# schematic.net
KiCad netlist of a schematic drawn in EAGLE
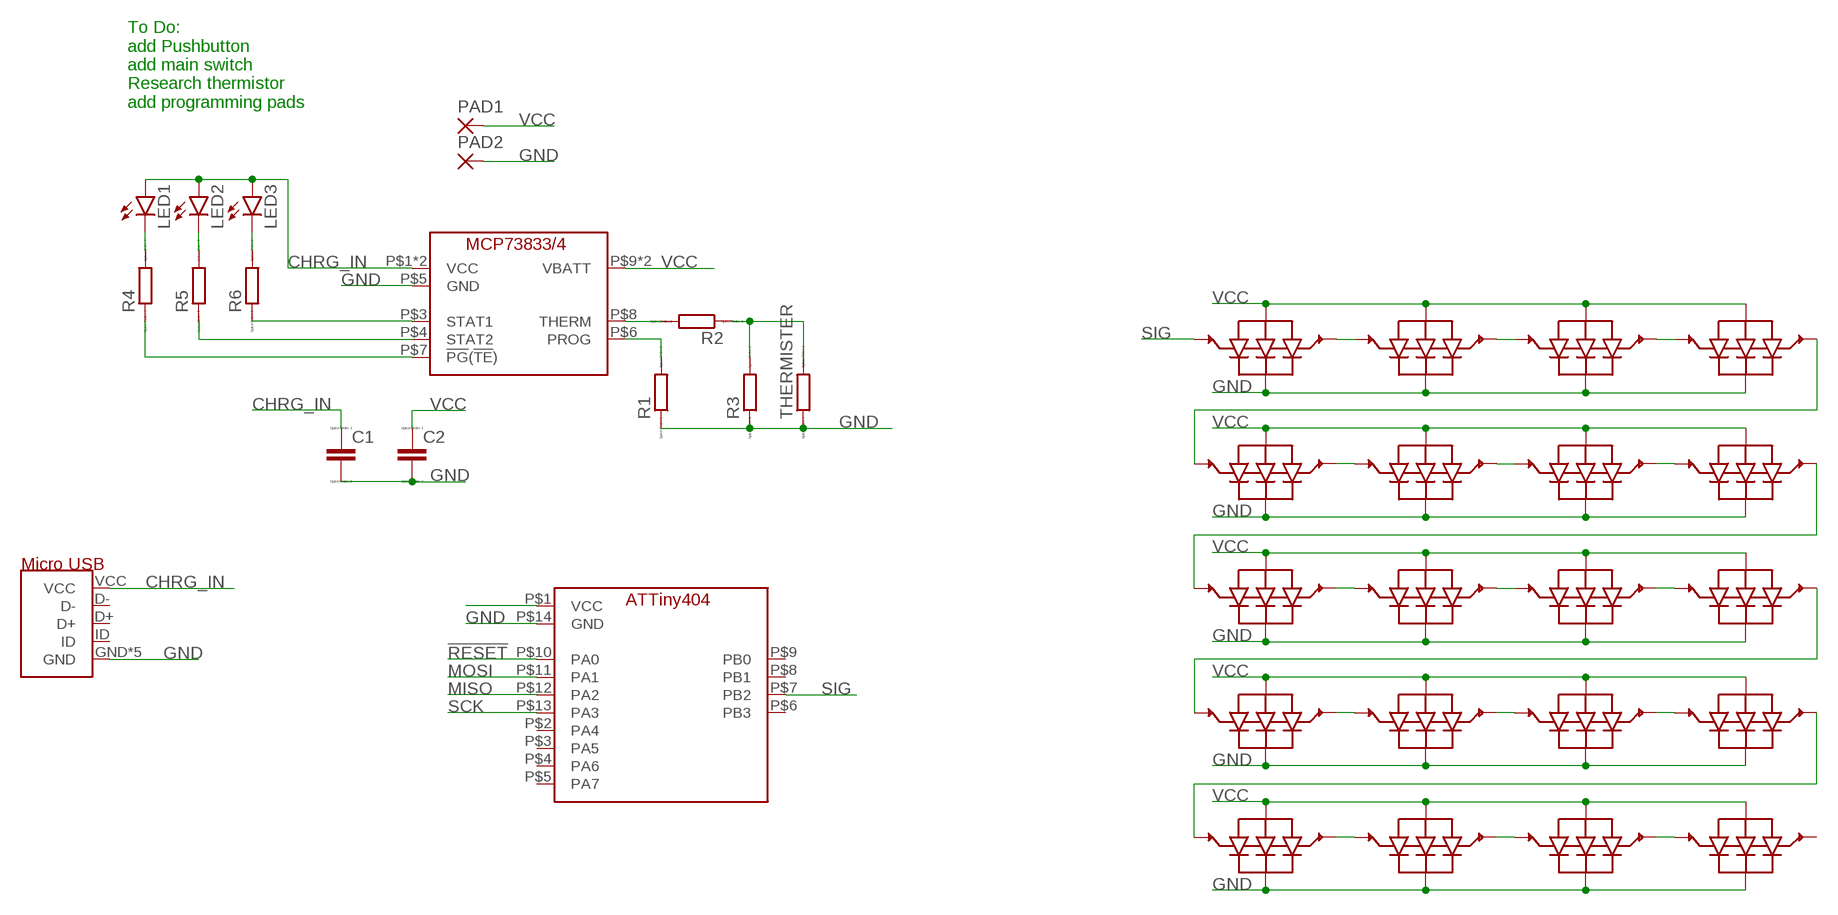
[diagram p0: schematic, sheet 1]

(export (version "E")
  (design (tool "Eeschema 10.0.6"))
  (components
    (comp (ref "C1")
      (value "CC1206")
      (footprint "eagle-import:C1206")
      (libsource (lib "eagle-import") (part "CC1206"))
    )
    (comp (ref "C2")
      (value "CC1206")
      (footprint "eagle-import:C1206")
      (libsource (lib "eagle-import") (part "CC1206"))
    )
    (comp (ref "LED1")
      (value "LEDSML1206")
      (footprint "eagle-import:SML1206")
      (libsource (lib "eagle-import") (part "LEDSML1206"))
    )
    (comp (ref "LED2")
      (value "LEDSML1206")
      (footprint "eagle-import:SML1206")
      (libsource (lib "eagle-import") (part "LEDSML1206"))
    )
    (comp (ref "LED3")
      (value "LEDSML1206")
      (footprint "eagle-import:SML1206")
      (libsource (lib "eagle-import") (part "LEDSML1206"))
    )
    (comp (ref "PAD1")
      (value "1,6/0,8")
      (footprint "eagle-import:1,6_0,8")
      (libsource (lib "eagle-import") (part "1,6/0,8"))
    )
    (comp (ref "PAD2")
      (value "1,6/0,8")
      (footprint "eagle-import:1,6_0,8")
      (libsource (lib "eagle-import") (part "1,6/0,8"))
    )
    (comp (ref "R1")
      (value "RR1206")
      (footprint "eagle-import:R1206")
      (libsource (lib "eagle-import") (part "RR1206"))
    )
    (comp (ref "R2")
      (value "RR1206")
      (footprint "eagle-import:R1206")
      (libsource (lib "eagle-import") (part "RR1206"))
    )
    (comp (ref "R3")
      (value "RR1206")
      (footprint "eagle-import:R1206")
      (libsource (lib "eagle-import") (part "RR1206"))
    )
    (comp (ref "R4")
      (value "RR1206")
      (footprint "eagle-import:R1206")
      (libsource (lib "eagle-import") (part "RR1206"))
    )
    (comp (ref "R5")
      (value "RR1206")
      (footprint "eagle-import:R1206")
      (libsource (lib "eagle-import") (part "RR1206"))
    )
    (comp (ref "R6")
      (value "RR1206")
      (footprint "eagle-import:R1206")
      (libsource (lib "eagle-import") (part "RR1206"))
    )
    (comp (ref "THERMISTER")
      (value "RR1206")
      (footprint "eagle-import:R1206")
      (libsource (lib "eagle-import") (part "RR1206"))
    )
    (comp (ref "U$1")
      (value "ATTINY404")
      (footprint "eagle-import:14-SOIC")
      (libsource (lib "eagle-import") (part "ATTINY404"))
    )
    (comp (ref "U$2")
      (value "MCP73833/4")
      (footprint "eagle-import:10-MSOP")
      (libsource (lib "eagle-import") (part "MCP73833/4"))
    )
    (comp (ref "U$3")
      (value "WS2812B")
      (footprint "eagle-import:5050-THRU")
      (libsource (lib "eagle-import") (part "WS2812B"))
    )
    (comp (ref "U$4")
      (value "WS2812B")
      (footprint "eagle-import:5050-THRU")
      (libsource (lib "eagle-import") (part "WS2812B"))
    )
    (comp (ref "U$5")
      (value "WS2812B")
      (footprint "eagle-import:5050-THRU")
      (libsource (lib "eagle-import") (part "WS2812B"))
    )
    (comp (ref "U$6")
      (value "WS2812B")
      (footprint "eagle-import:5050-THRU")
      (libsource (lib "eagle-import") (part "WS2812B"))
    )
    (comp (ref "U$7")
      (value "WS2812B")
      (footprint "eagle-import:5050-THRU")
      (libsource (lib "eagle-import") (part "WS2812B"))
    )
    (comp (ref "U$8")
      (value "WS2812B")
      (footprint "eagle-import:5050-THRU")
      (libsource (lib "eagle-import") (part "WS2812B"))
    )
    (comp (ref "U$9")
      (value "WS2812B")
      (footprint "eagle-import:5050-THRU")
      (libsource (lib "eagle-import") (part "WS2812B"))
    )
    (comp (ref "U$10")
      (value "WS2812B")
      (footprint "eagle-import:5050-THRU")
      (libsource (lib "eagle-import") (part "WS2812B"))
    )
    (comp (ref "U$11")
      (value "WS2812B")
      (footprint "eagle-import:5050-THRU")
      (libsource (lib "eagle-import") (part "WS2812B"))
    )
    (comp (ref "U$12")
      (value "WS2812B")
      (footprint "eagle-import:5050-THRU")
      (libsource (lib "eagle-import") (part "WS2812B"))
    )
    (comp (ref "U$13")
      (value "WS2812B")
      (footprint "eagle-import:5050-THRU")
      (libsource (lib "eagle-import") (part "WS2812B"))
    )
    (comp (ref "U$14")
      (value "WS2812B")
      (footprint "eagle-import:5050-THRU")
      (libsource (lib "eagle-import") (part "WS2812B"))
    )
    (comp (ref "U$15")
      (value "WS2812B")
      (footprint "eagle-import:5050-THRU")
      (libsource (lib "eagle-import") (part "WS2812B"))
    )
    (comp (ref "U$16")
      (value "WS2812B")
      (footprint "eagle-import:5050-THRU")
      (libsource (lib "eagle-import") (part "WS2812B"))
    )
    (comp (ref "U$17")
      (value "WS2812B")
      (footprint "eagle-import:5050-THRU")
      (libsource (lib "eagle-import") (part "WS2812B"))
    )
    (comp (ref "U$18")
      (value "WS2812B")
      (footprint "eagle-import:5050-THRU")
      (libsource (lib "eagle-import") (part "WS2812B"))
    )
    (comp (ref "U$19")
      (value "WS2812B")
      (footprint "eagle-import:5050-THRU")
      (libsource (lib "eagle-import") (part "WS2812B"))
    )
    (comp (ref "U$20")
      (value "WS2812B")
      (footprint "eagle-import:5050-THRU")
      (libsource (lib "eagle-import") (part "WS2812B"))
    )
    (comp (ref "U$21")
      (value "WS2812B")
      (footprint "eagle-import:5050-THRU")
      (libsource (lib "eagle-import") (part "WS2812B"))
    )
    (comp (ref "U$22")
      (value "WS2812B")
      (footprint "eagle-import:5050-THRU")
      (libsource (lib "eagle-import") (part "WS2812B"))
    )
    (comp (ref "U$23")
      (value "MICROUSB")
      (footprint "eagle-import:MICROUSB")
      (libsource (lib "eagle-import") (part "MICROUSB"))
    )
  )
  (nets
    (net (code "1") (name "/CHRG_IN") (class "Default")
      (node (ref "C1") (pin "1") (pinfunction "1_1") (pintype "passive"))
      (node (ref "LED1") (pin "A") (pinfunction "A_A") (pintype "passive"))
      (node (ref "LED2") (pin "A") (pinfunction "A_A") (pintype "passive"))
      (node (ref "LED3") (pin "A") (pinfunction "A_A") (pintype "passive"))
      (node (ref "U$2") (pin "P$1") (pinfunction "VCC_P$1") (pintype "bidirectional"))
      (node (ref "U$2") (pin "P$2") (pinfunction "VCC_P$2") (pintype "bidirectional"))
      (node (ref "U$23") (pin "VCC") (pinfunction "VCC_VCC") (pintype "bidirectional"))
    )
    (net (code "2") (name "/GND") (class "Default")
      (node (ref "C1") (pin "2") (pinfunction "2_2") (pintype "passive"))
      (node (ref "C2") (pin "2") (pinfunction "2_2") (pintype "passive"))
      (node (ref "PAD2") (pin "1") (pinfunction "P_1") (pintype "passive"))
      (node (ref "R1") (pin "1") (pinfunction "1_1") (pintype "passive"))
      (node (ref "R3") (pin "1") (pinfunction "1_1") (pintype "passive"))
      (node (ref "THERMISTER") (pin "1") (pinfunction "1_1") (pintype "passive"))
      (node (ref "U$1") (pin "P$14") (pinfunction "GND_P$14") (pintype "bidirectional"))
      (node (ref "U$10") (pin "P$3") (pinfunction "GND_P$3") (pintype "bidirectional"))
      (node (ref "U$11") (pin "P$3") (pinfunction "GND_P$3") (pintype "bidirectional"))
      (node (ref "U$12") (pin "P$3") (pinfunction "GND_P$3") (pintype "bidirectional"))
      (node (ref "U$13") (pin "P$3") (pinfunction "GND_P$3") (pintype "bidirectional"))
      (node (ref "U$14") (pin "P$3") (pinfunction "GND_P$3") (pintype "bidirectional"))
      (node (ref "U$15") (pin "P$3") (pinfunction "GND_P$3") (pintype "bidirectional"))
      (node (ref "U$16") (pin "P$3") (pinfunction "GND_P$3") (pintype "bidirectional"))
      (node (ref "U$17") (pin "P$3") (pinfunction "GND_P$3") (pintype "bidirectional"))
      (node (ref "U$18") (pin "P$3") (pinfunction "GND_P$3") (pintype "bidirectional"))
      (node (ref "U$19") (pin "P$3") (pinfunction "GND_P$3") (pintype "bidirectional"))
      (node (ref "U$2") (pin "P$5") (pinfunction "GND_P$5") (pintype "bidirectional"))
      (node (ref "U$20") (pin "P$3") (pinfunction "GND_P$3") (pintype "bidirectional"))
      (node (ref "U$21") (pin "P$3") (pinfunction "GND_P$3") (pintype "bidirectional"))
      (node (ref "U$22") (pin "P$3") (pinfunction "GND_P$3") (pintype "bidirectional"))
      (node (ref "U$23") (pin "GND") (pinfunction "GND_GND") (pintype "bidirectional"))
      (node (ref "U$23") (pin "GND2") (pinfunction "GND_GND2") (pintype "bidirectional"))
      (node (ref "U$23") (pin "GND3") (pinfunction "GND_GND3") (pintype "bidirectional"))
      (node (ref "U$23") (pin "GND4") (pinfunction "GND_GND4") (pintype "bidirectional"))
      (node (ref "U$23") (pin "GND5") (pinfunction "GND_GND5") (pintype "bidirectional"))
      (node (ref "U$3") (pin "P$3") (pinfunction "GND_P$3") (pintype "bidirectional"))
      (node (ref "U$4") (pin "P$3") (pinfunction "GND_P$3") (pintype "bidirectional"))
      (node (ref "U$5") (pin "P$3") (pinfunction "GND_P$3") (pintype "bidirectional"))
      (node (ref "U$6") (pin "P$3") (pinfunction "GND_P$3") (pintype "bidirectional"))
      (node (ref "U$7") (pin "P$3") (pinfunction "GND_P$3") (pintype "bidirectional"))
      (node (ref "U$8") (pin "P$3") (pinfunction "GND_P$3") (pintype "bidirectional"))
      (node (ref "U$9") (pin "P$3") (pinfunction "GND_P$3") (pintype "bidirectional"))
    )
    (net (code "3") (name "/MISO") (class "Default")
      (node (ref "U$1") (pin "P$12") (pinfunction "PA2_P$12") (pintype "bidirectional"))
    )
    (net (code "4") (name "/MOSI") (class "Default")
      (node (ref "U$1") (pin "P$11") (pinfunction "PA1_P$11") (pintype "bidirectional"))
    )
    (net (code "5") (name "/SCK") (class "Default")
      (node (ref "U$1") (pin "P$13") (pinfunction "PA3_P$13") (pintype "bidirectional"))
    )
    (net (code "6") (name "/SIG") (class "Default")
      (node (ref "U$1") (pin "P$7") (pinfunction "PB2_P$7") (pintype "bidirectional"))
      (node (ref "U$10") (pin "P$4") (pinfunction "DIN_P$4") (pintype "bidirectional"))
    )
    (net (code "7") (name "/VCC") (class "Default")
      (node (ref "C2") (pin "1") (pinfunction "1_1") (pintype "passive"))
      (node (ref "PAD1") (pin "1") (pinfunction "P_1") (pintype "passive"))
      (node (ref "U$10") (pin "P$1") (pinfunction "VCC_P$1") (pintype "bidirectional"))
      (node (ref "U$11") (pin "P$1") (pinfunction "VCC_P$1") (pintype "bidirectional"))
      (node (ref "U$12") (pin "P$1") (pinfunction "VCC_P$1") (pintype "bidirectional"))
      (node (ref "U$13") (pin "P$1") (pinfunction "VCC_P$1") (pintype "bidirectional"))
      (node (ref "U$14") (pin "P$1") (pinfunction "VCC_P$1") (pintype "bidirectional"))
      (node (ref "U$15") (pin "P$1") (pinfunction "VCC_P$1") (pintype "bidirectional"))
      (node (ref "U$16") (pin "P$1") (pinfunction "VCC_P$1") (pintype "bidirectional"))
      (node (ref "U$17") (pin "P$1") (pinfunction "VCC_P$1") (pintype "bidirectional"))
      (node (ref "U$18") (pin "P$1") (pinfunction "VCC_P$1") (pintype "bidirectional"))
      (node (ref "U$19") (pin "P$1") (pinfunction "VCC_P$1") (pintype "bidirectional"))
      (node (ref "U$2") (pin "P$10") (pinfunction "VBATT_P$10") (pintype "bidirectional"))
      (node (ref "U$2") (pin "P$9") (pinfunction "VBATT_P$9") (pintype "bidirectional"))
      (node (ref "U$20") (pin "P$1") (pinfunction "VCC_P$1") (pintype "bidirectional"))
      (node (ref "U$21") (pin "P$1") (pinfunction "VCC_P$1") (pintype "bidirectional"))
      (node (ref "U$22") (pin "P$1") (pinfunction "VCC_P$1") (pintype "bidirectional"))
      (node (ref "U$3") (pin "P$1") (pinfunction "VCC_P$1") (pintype "bidirectional"))
      (node (ref "U$4") (pin "P$1") (pinfunction "VCC_P$1") (pintype "bidirectional"))
      (node (ref "U$5") (pin "P$1") (pinfunction "VCC_P$1") (pintype "bidirectional"))
      (node (ref "U$6") (pin "P$1") (pinfunction "VCC_P$1") (pintype "bidirectional"))
      (node (ref "U$7") (pin "P$1") (pinfunction "VCC_P$1") (pintype "bidirectional"))
      (node (ref "U$8") (pin "P$1") (pinfunction "VCC_P$1") (pintype "bidirectional"))
      (node (ref "U$9") (pin "P$1") (pinfunction "VCC_P$1") (pintype "bidirectional"))
    )
    (net (code "8") (name "/~{RESET}") (class "Default")
      (node (ref "U$1") (pin "P$10") (pinfunction "PA0_P$10") (pintype "bidirectional"))
    )
    (net (code "9") (name "Net-(LED1-PadC)") (class "Default")
      (node (ref "LED1") (pin "C") (pinfunction "C_C") (pintype "passive"))
      (node (ref "R4") (pin "2") (pinfunction "2_2") (pintype "passive"))
    )
    (net (code "10") (name "Net-(LED2-PadC)") (class "Default")
      (node (ref "LED2") (pin "C") (pinfunction "C_C") (pintype "passive"))
      (node (ref "R5") (pin "2") (pinfunction "2_2") (pintype "passive"))
    )
    (net (code "11") (name "Net-(LED3-PadC)") (class "Default")
      (node (ref "LED3") (pin "C") (pinfunction "C_C") (pintype "passive"))
      (node (ref "R6") (pin "2") (pinfunction "2_2") (pintype "passive"))
    )
    (net (code "12") (name "Net-(R2-Pad1)") (class "Default")
      (node (ref "R2") (pin "1") (pinfunction "1_1") (pintype "passive"))
      (node (ref "R3") (pin "2") (pinfunction "2_2") (pintype "passive"))
      (node (ref "THERMISTER") (pin "2") (pinfunction "2_2") (pintype "passive"))
    )
    (net (code "13") (name "Net-(U$2-PROG)") (class "Default")
      (node (ref "R1") (pin "2") (pinfunction "2_2") (pintype "passive"))
      (node (ref "U$2") (pin "P$6") (pinfunction "PROG_P$6") (pintype "bidirectional"))
    )
    (net (code "14") (name "Net-(U$2-STAT1)") (class "Default")
      (node (ref "R6") (pin "1") (pinfunction "1_1") (pintype "passive"))
      (node (ref "U$2") (pin "P$3") (pinfunction "STAT1_P$3") (pintype "bidirectional"))
    )
    (net (code "15") (name "Net-(U$2-STAT2)") (class "Default")
      (node (ref "R5") (pin "1") (pinfunction "1_1") (pintype "passive"))
      (node (ref "U$2") (pin "P$4") (pinfunction "STAT2_P$4") (pintype "bidirectional"))
    )
    (net (code "16") (name "Net-(U$2-THERM)") (class "Default")
      (node (ref "R2") (pin "2") (pinfunction "2_2") (pintype "passive"))
      (node (ref "U$2") (pin "P$8") (pinfunction "THERM_P$8") (pintype "bidirectional"))
    )
    (net (code "17") (name "Net-(U$2-~{PG}(~{TE}))") (class "Default")
      (node (ref "R4") (pin "1") (pinfunction "1_1") (pintype "passive"))
      (node (ref "U$2") (pin "P$7") (pinfunction "~{PG}(~{TE})_P$7") (pintype "bidirectional"))
    )
    (net (code "18") (name "Net-(U$3-DOUT)") (class "Default")
      (node (ref "U$3") (pin "P$2") (pinfunction "DOUT_P$2") (pintype "bidirectional"))
      (node (ref "U$4") (pin "P$4") (pinfunction "DIN_P$4") (pintype "bidirectional"))
    )
    (net (code "19") (name "Net-(U$4-DOUT)") (class "Default")
      (node (ref "U$4") (pin "P$2") (pinfunction "DOUT_P$2") (pintype "bidirectional"))
      (node (ref "U$5") (pin "P$4") (pinfunction "DIN_P$4") (pintype "bidirectional"))
    )
    (net (code "20") (name "Net-(U$5-DOUT)") (class "Default")
      (node (ref "U$5") (pin "P$2") (pinfunction "DOUT_P$2") (pintype "bidirectional"))
      (node (ref "U$6") (pin "P$4") (pinfunction "DIN_P$4") (pintype "bidirectional"))
    )
    (net (code "21") (name "Net-(U$6-DOUT)") (class "Default")
      (node (ref "U$6") (pin "P$2") (pinfunction "DOUT_P$2") (pintype "bidirectional"))
      (node (ref "U$7") (pin "P$4") (pinfunction "DIN_P$4") (pintype "bidirectional"))
    )
    (net (code "22") (name "Net-(U$7-DOUT)") (class "Default")
      (node (ref "U$7") (pin "P$2") (pinfunction "DOUT_P$2") (pintype "bidirectional"))
      (node (ref "U$8") (pin "P$4") (pinfunction "DIN_P$4") (pintype "bidirectional"))
    )
    (net (code "23") (name "Net-(U$8-DOUT)") (class "Default")
      (node (ref "U$8") (pin "P$2") (pinfunction "DOUT_P$2") (pintype "bidirectional"))
      (node (ref "U$9") (pin "P$4") (pinfunction "DIN_P$4") (pintype "bidirectional"))
    )
    (net (code "24") (name "Net-(U$10-DOUT)") (class "Default")
      (node (ref "U$10") (pin "P$2") (pinfunction "DOUT_P$2") (pintype "bidirectional"))
      (node (ref "U$11") (pin "P$4") (pinfunction "DIN_P$4") (pintype "bidirectional"))
    )
    (net (code "25") (name "Net-(U$11-DOUT)") (class "Default")
      (node (ref "U$11") (pin "P$2") (pinfunction "DOUT_P$2") (pintype "bidirectional"))
      (node (ref "U$12") (pin "P$4") (pinfunction "DIN_P$4") (pintype "bidirectional"))
    )
    (net (code "26") (name "Net-(U$12-DOUT)") (class "Default")
      (node (ref "U$12") (pin "P$2") (pinfunction "DOUT_P$2") (pintype "bidirectional"))
      (node (ref "U$13") (pin "P$4") (pinfunction "DIN_P$4") (pintype "bidirectional"))
    )
    (net (code "27") (name "Net-(U$13-DOUT)") (class "Default")
      (node (ref "U$13") (pin "P$2") (pinfunction "DOUT_P$2") (pintype "bidirectional"))
      (node (ref "U$19") (pin "P$4") (pinfunction "DIN_P$4") (pintype "bidirectional"))
    )
    (net (code "28") (name "Net-(U$14-DIN)") (class "Default")
      (node (ref "U$14") (pin "P$4") (pinfunction "DIN_P$4") (pintype "bidirectional"))
      (node (ref "U$9") (pin "P$2") (pinfunction "DOUT_P$2") (pintype "bidirectional"))
    )
    (net (code "29") (name "Net-(U$14-DOUT)") (class "Default")
      (node (ref "U$14") (pin "P$2") (pinfunction "DOUT_P$2") (pintype "bidirectional"))
      (node (ref "U$15") (pin "P$4") (pinfunction "DIN_P$4") (pintype "bidirectional"))
    )
    (net (code "30") (name "Net-(U$15-DOUT)") (class "Default")
      (node (ref "U$15") (pin "P$2") (pinfunction "DOUT_P$2") (pintype "bidirectional"))
      (node (ref "U$16") (pin "P$4") (pinfunction "DIN_P$4") (pintype "bidirectional"))
    )
    (net (code "31") (name "Net-(U$16-DOUT)") (class "Default")
      (node (ref "U$16") (pin "P$2") (pinfunction "DOUT_P$2") (pintype "bidirectional"))
      (node (ref "U$17") (pin "P$4") (pinfunction "DIN_P$4") (pintype "bidirectional"))
    )
    (net (code "32") (name "Net-(U$17-DOUT)") (class "Default")
      (node (ref "U$17") (pin "P$2") (pinfunction "DOUT_P$2") (pintype "bidirectional"))
      (node (ref "U$18") (pin "P$4") (pinfunction "DIN_P$4") (pintype "bidirectional"))
    )
    (net (code "33") (name "Net-(U$18-DOUT)") (class "Default")
      (node (ref "U$18") (pin "P$2") (pinfunction "DOUT_P$2") (pintype "bidirectional"))
      (node (ref "U$20") (pin "P$4") (pinfunction "DIN_P$4") (pintype "bidirectional"))
    )
    (net (code "34") (name "Net-(U$19-DOUT)") (class "Default")
      (node (ref "U$19") (pin "P$2") (pinfunction "DOUT_P$2") (pintype "bidirectional"))
      (node (ref "U$3") (pin "P$4") (pinfunction "DIN_P$4") (pintype "bidirectional"))
    )
    (net (code "35") (name "Net-(U$20-DOUT)") (class "Default")
      (node (ref "U$20") (pin "P$2") (pinfunction "DOUT_P$2") (pintype "bidirectional"))
      (node (ref "U$21") (pin "P$4") (pinfunction "DIN_P$4") (pintype "bidirectional"))
    )
    (net (code "36") (name "Net-(U$21-DOUT)") (class "Default")
      (node (ref "U$21") (pin "P$2") (pinfunction "DOUT_P$2") (pintype "bidirectional"))
      (node (ref "U$22") (pin "P$4") (pinfunction "DIN_P$4") (pintype "bidirectional"))
    )
    (net (code "37") (name "unconnected-(U$1-PA4-PadP$2)") (class "Default")
      (node (ref "U$1") (pin "P$2") (pinfunction "PA4_P$2") (pintype "bidirectional"))
    )
    (net (code "38") (name "unconnected-(U$1-PA5-PadP$3)") (class "Default")
      (node (ref "U$1") (pin "P$3") (pinfunction "PA5_P$3") (pintype "bidirectional"))
    )
    (net (code "39") (name "unconnected-(U$1-PA6-PadP$4)") (class "Default")
      (node (ref "U$1") (pin "P$4") (pinfunction "PA6_P$4") (pintype "bidirectional"))
    )
    (net (code "40") (name "unconnected-(U$1-PA7-PadP$5)") (class "Default")
      (node (ref "U$1") (pin "P$5") (pinfunction "PA7_P$5") (pintype "bidirectional"))
    )
    (net (code "41") (name "unconnected-(U$1-PB0-PadP$9)") (class "Default")
      (node (ref "U$1") (pin "P$9") (pinfunction "PB0_P$9") (pintype "bidirectional"))
    )
    (net (code "42") (name "unconnected-(U$1-PB1-PadP$8)") (class "Default")
      (node (ref "U$1") (pin "P$8") (pinfunction "PB1_P$8") (pintype "bidirectional"))
    )
    (net (code "43") (name "unconnected-(U$1-PB3-PadP$6)") (class "Default")
      (node (ref "U$1") (pin "P$6") (pinfunction "PB3_P$6") (pintype "bidirectional"))
    )
    (net (code "44") (name "unconnected-(U$1-VCC-PadP$1)") (class "Default")
      (node (ref "U$1") (pin "P$1") (pinfunction "VCC_P$1") (pintype "bidirectional"))
    )
    (net (code "45") (name "unconnected-(U$22-DOUT-PadP$2)") (class "Default")
      (node (ref "U$22") (pin "P$2") (pinfunction "DOUT_P$2") (pintype "bidirectional"))
    )
    (net (code "46") (name "unconnected-(U$23-PadD+)") (class "Default")
      (node (ref "U$23") (pin "D+") (pinfunction "D+_D+") (pintype "bidirectional"))
    )
    (net (code "47") (name "unconnected-(U$23-PadD-)") (class "Default")
      (node (ref "U$23") (pin "D-") (pinfunction "D-_D-") (pintype "bidirectional"))
    )
    (net (code "48") (name "unconnected-(U$23-PadID)") (class "Default")
      (node (ref "U$23") (pin "ID") (pinfunction "ID_ID") (pintype "bidirectional"))
    )
  )
)
